# Newschem.net
KiCad netlist of a schematic drawn in EAGLE
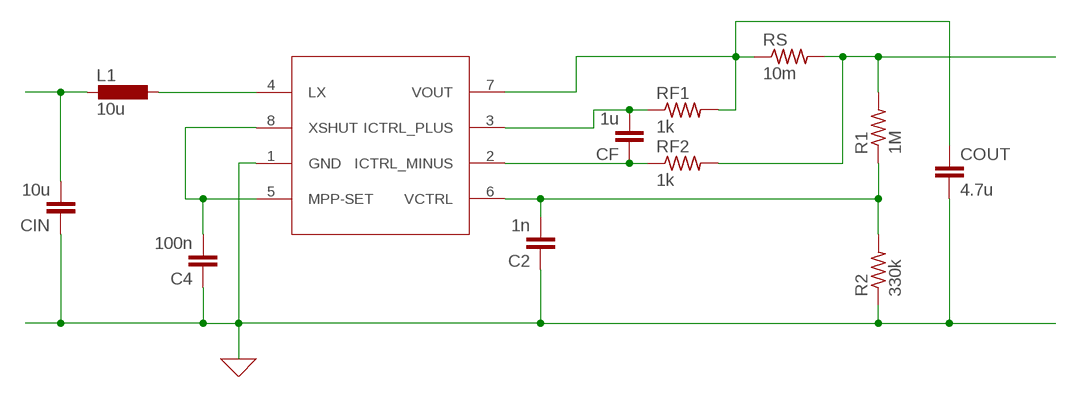
[diagram p0: schematic, sheet 1]

(export (version "E")
  (design (tool "Eeschema 10.0.6"))
  (components
    (comp (ref "C2")
      (value "1n")
      (footprint "eagle-import:C025-025X050")
      (libsource (lib "eagle-import") (part "C-EU025-025X050"))
    )
    (comp (ref "C4")
      (value "100n")
      (footprint "eagle-import:C025-025X050")
      (libsource (lib "eagle-import") (part "C-EU025-025X050"))
    )
    (comp (ref "CF")
      (value "1u")
      (footprint "eagle-import:C025-025X050")
      (libsource (lib "eagle-import") (part "C-EU025-025X050"))
    )
    (comp (ref "CIN")
      (value "10u")
      (footprint "eagle-import:C025-025X050")
      (libsource (lib "eagle-import") (part "C-EU025-025X050"))
    )
    (comp (ref "COUT")
      (value "4.7u")
      (footprint "eagle-import:C025-025X050")
      (libsource (lib "eagle-import") (part "C-EU025-025X050"))
    )
    (comp (ref "L1")
      (value "10u")
      (footprint "eagle-import:DO3316P")
      (libsource (lib "eagle-import") (part "DO3316P"))
    )
    (comp (ref "R1")
      (value "1M")
      (footprint "eagle-import:0204V")
      (libsource (lib "eagle-import") (part "R-US_0204/2V"))
    )
    (comp (ref "R2")
      (value "330k")
      (footprint "eagle-import:0204V")
      (libsource (lib "eagle-import") (part "R-US_0204/2V"))
    )
    (comp (ref "RF1")
      (value "1k")
      (footprint "eagle-import:0204V")
      (libsource (lib "eagle-import") (part "R-US_0204/2V"))
    )
    (comp (ref "RF2")
      (value "1k")
      (footprint "eagle-import:0204V")
      (libsource (lib "eagle-import") (part "R-US_0204/2V"))
    )
    (comp (ref "RS")
      (value "10m")
      (footprint "eagle-import:0204V")
      (libsource (lib "eagle-import") (part "R-US_0204/2V"))
    )
    (comp (ref "U$1")
      (value "SPV1040")
      (footprint "eagle-import:SOP65P640X120-8N")
      (libsource (lib "eagle-import") (part "SPV1040"))
    )
  )
  (nets
    (net (code "1") (name "GND") (class "Default")
      (node (ref "C2") (pin "1") (pinfunction "1_1") (pintype "passive"))
      (node (ref "C4") (pin "1") (pinfunction "1_1") (pintype "passive"))
      (node (ref "CIN") (pin "1") (pinfunction "1_1") (pintype "passive"))
      (node (ref "COUT") (pin "2") (pinfunction "2_2") (pintype "passive"))
      (node (ref "R2") (pin "1") (pinfunction "1_1") (pintype "passive"))
      (node (ref "U$1") (pin "1") (pinfunction "GND_1") (pintype "bidirectional"))
    )
    (net (code "2") (name "Net-(CIN-Pad2)") (class "Default")
      (node (ref "CIN") (pin "2") (pinfunction "2_2") (pintype "passive"))
      (node (ref "L1") (pin "1") (pinfunction "1_1") (pintype "passive"))
    )
    (net (code "3") (name "Net-(R1-Pad2)") (class "Default")
      (node (ref "R1") (pin "2") (pinfunction "2_2") (pintype "passive"))
      (node (ref "RF2") (pin "2") (pinfunction "2_2") (pintype "passive"))
      (node (ref "RS") (pin "2") (pinfunction "2_2") (pintype "passive"))
    )
    (net (code "4") (name "Net-(U$1-ICTRL_MINUS)") (class "Default")
      (node (ref "CF") (pin "1") (pinfunction "1_1") (pintype "passive"))
      (node (ref "RF2") (pin "1") (pinfunction "1_1") (pintype "passive"))
      (node (ref "U$1") (pin "2") (pinfunction "ICTRL_MINUS_2") (pintype "bidirectional"))
    )
    (net (code "5") (name "Net-(U$1-ICTRL_PLUS)") (class "Default")
      (node (ref "CF") (pin "2") (pinfunction "2_2") (pintype "passive"))
      (node (ref "RF1") (pin "1") (pinfunction "1_1") (pintype "passive"))
      (node (ref "U$1") (pin "3") (pinfunction "ICTRL_PLUS_3") (pintype "bidirectional"))
    )
    (net (code "6") (name "Net-(U$1-LX)") (class "Default")
      (node (ref "L1") (pin "2") (pinfunction "2_2") (pintype "passive"))
      (node (ref "U$1") (pin "4") (pinfunction "LX_4") (pintype "bidirectional"))
    )
    (net (code "7") (name "Net-(U$1-MPP-SET)") (class "Default")
      (node (ref "C4") (pin "2") (pinfunction "2_2") (pintype "passive"))
      (node (ref "U$1") (pin "5") (pinfunction "MPP-SET_5") (pintype "bidirectional"))
      (node (ref "U$1") (pin "8") (pinfunction "XSHUT_8") (pintype "bidirectional"))
    )
    (net (code "8") (name "Net-(U$1-VCTRL)") (class "Default")
      (node (ref "C2") (pin "2") (pinfunction "2_2") (pintype "passive"))
      (node (ref "R1") (pin "1") (pinfunction "1_1") (pintype "passive"))
      (node (ref "R2") (pin "2") (pinfunction "2_2") (pintype "passive"))
      (node (ref "U$1") (pin "6") (pinfunction "VCTRL_6") (pintype "bidirectional"))
    )
    (net (code "9") (name "Net-(U$1-VOUT)") (class "Default")
      (node (ref "COUT") (pin "1") (pinfunction "1_1") (pintype "passive"))
      (node (ref "RF1") (pin "2") (pinfunction "2_2") (pintype "passive"))
      (node (ref "RS") (pin "1") (pinfunction "1_1") (pintype "passive"))
      (node (ref "U$1") (pin "7") (pinfunction "VOUT_7") (pintype "bidirectional"))
    )
  )
)
